# main.net
KiCad netlist of a schematic drawn in EAGLE
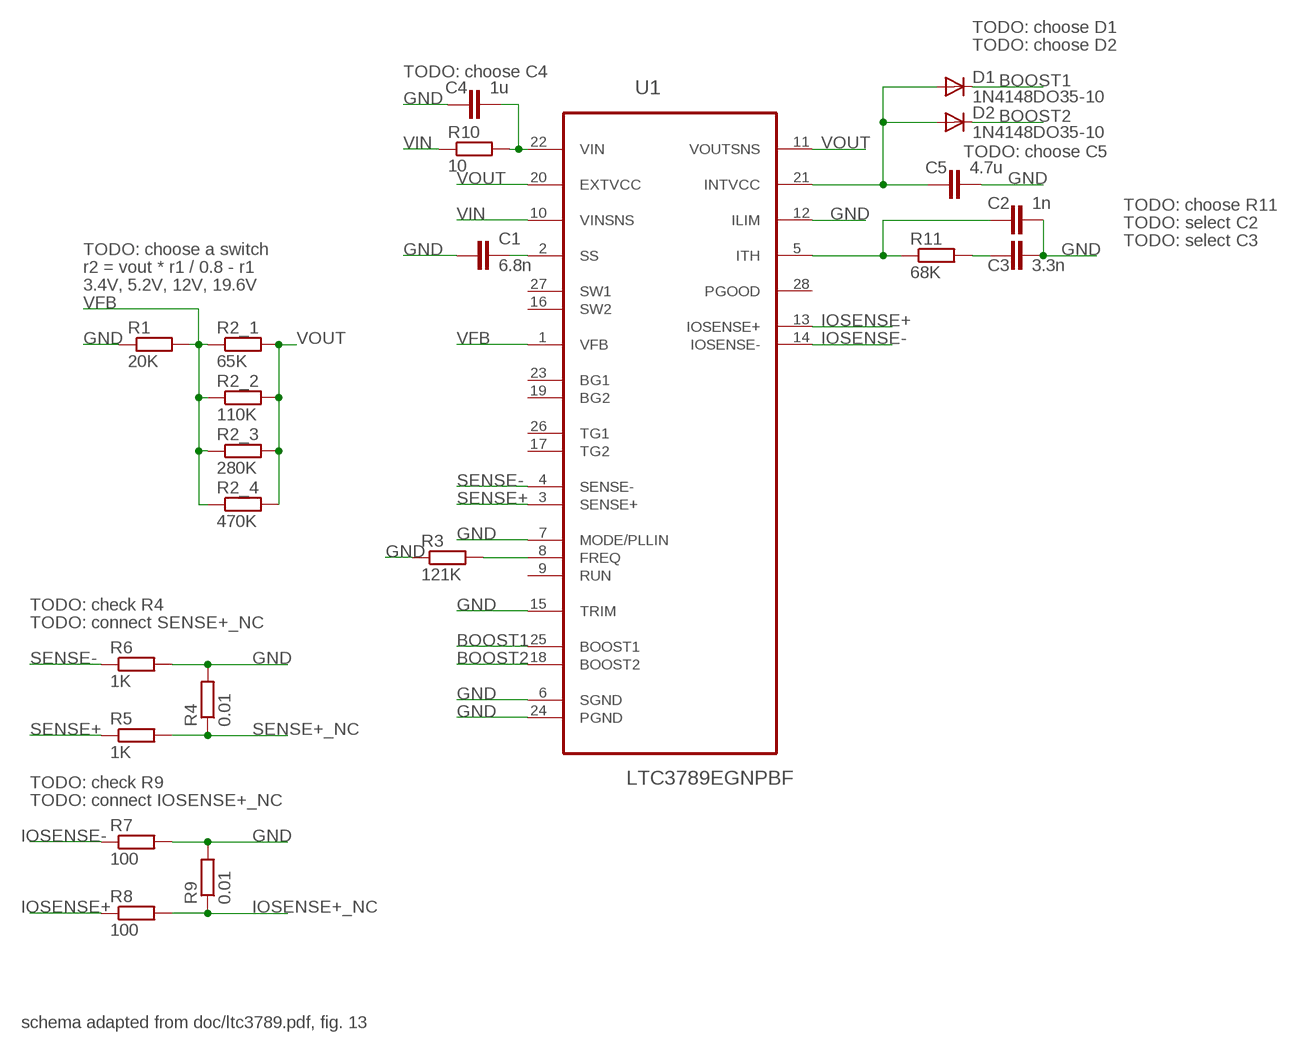
[diagram p0: schematic, sheet 1]

(export (version "E")
  (design (tool "Eeschema 10.0.6"))
  (components
    (comp (ref "C1")
      (value "6.8n")
      (footprint "eagle-import:C1206K")
      (libsource (lib "eagle-import") (part "C-EUC1206K"))
    )
    (comp (ref "C2")
      (value "1n")
      (footprint "eagle-import:C1206K")
      (libsource (lib "eagle-import") (part "C-EUC1206K"))
    )
    (comp (ref "C3")
      (value "3.3n")
      (footprint "eagle-import:C1206K")
      (libsource (lib "eagle-import") (part "C-EUC1206K"))
    )
    (comp (ref "C4")
      (value "1u")
      (footprint "eagle-import:C1206K")
      (libsource (lib "eagle-import") (part "C-EUC1206K"))
    )
    (comp (ref "C5")
      (value "4.7u")
      (footprint "eagle-import:C1206K")
      (libsource (lib "eagle-import") (part "C-EUC1206K"))
    )
    (comp (ref "D1")
      (value "1N4148DO35-10")
      (footprint "eagle-import:DO35-10")
      (libsource (lib "eagle-import") (part "1N4148DO35-10"))
    )
    (comp (ref "D2")
      (value "1N4148DO35-10")
      (footprint "eagle-import:DO35-10")
      (libsource (lib "eagle-import") (part "1N4148DO35-10"))
    )
    (comp (ref "R1")
      (value "20K")
      (footprint "eagle-import:R1206")
      (libsource (lib "eagle-import") (part "R-EU_R1206"))
    )
    (comp (ref "R2_1")
      (value "65K")
      (footprint "eagle-import:R1206")
      (libsource (lib "eagle-import") (part "R-EU_R1206"))
    )
    (comp (ref "R2_2")
      (value "110K")
      (footprint "eagle-import:R1206")
      (libsource (lib "eagle-import") (part "R-EU_R1206"))
    )
    (comp (ref "R2_3")
      (value "280K")
      (footprint "eagle-import:R1206")
      (libsource (lib "eagle-import") (part "R-EU_R1206"))
    )
    (comp (ref "R2_4")
      (value "470K")
      (footprint "eagle-import:R1206")
      (libsource (lib "eagle-import") (part "R-EU_R1206"))
    )
    (comp (ref "R3")
      (value "121K")
      (footprint "eagle-import:R1206")
      (libsource (lib "eagle-import") (part "R-EU_R1206"))
    )
    (comp (ref "R4")
      (value "0.01")
      (footprint "eagle-import:R1206")
      (libsource (lib "eagle-import") (part "R-EU_R1206"))
    )
    (comp (ref "R5")
      (value "1K")
      (footprint "eagle-import:R1206")
      (libsource (lib "eagle-import") (part "R-EU_R1206"))
    )
    (comp (ref "R6")
      (value "1K")
      (footprint "eagle-import:R1206")
      (libsource (lib "eagle-import") (part "R-EU_R1206"))
    )
    (comp (ref "R7")
      (value "100")
      (footprint "eagle-import:R1206")
      (libsource (lib "eagle-import") (part "R-EU_R1206"))
    )
    (comp (ref "R8")
      (value "100")
      (footprint "eagle-import:R1206")
      (libsource (lib "eagle-import") (part "R-EU_R1206"))
    )
    (comp (ref "R9")
      (value "0.01")
      (footprint "eagle-import:R1206")
      (libsource (lib "eagle-import") (part "R-EU_R1206"))
    )
    (comp (ref "R10")
      (value "10")
      (footprint "eagle-import:R1206")
      (libsource (lib "eagle-import") (part "R-EU_R1206"))
    )
    (comp (ref "R11")
      (value "68K")
      (footprint "eagle-import:R1206")
      (libsource (lib "eagle-import") (part "R-EU_R1206"))
    )
    (comp (ref "U1")
      (value "LTC3789EGNPBF")
      (footprint "eagle-import:SOP65P640X120-28N")
      (fields (field (name "MPN") "LTC3789EGN#PBF"))
      (libsource (lib "eagle-import") (part "LTC3789EGNPBF"))
    )
  )
  (nets
    (net (code "1") (name "/BOOST1") (class "Default")
      (node (ref "D1") (pin "C") (pinfunction "C_C") (pintype "passive"))
      (node (ref "U1") (pin "25") (pinfunction "BOOST1_25") (pintype "input"))
    )
    (net (code "2") (name "/BOOST2") (class "Default")
      (node (ref "D2") (pin "C") (pinfunction "C_C") (pintype "passive"))
      (node (ref "U1") (pin "18") (pinfunction "BOOST2_18") (pintype "input"))
    )
    (net (code "3") (name "/GND") (class "Default")
      (node (ref "C1") (pin "1") (pinfunction "1_1") (pintype "passive"))
      (node (ref "C2") (pin "2") (pinfunction "2_2") (pintype "passive"))
      (node (ref "C3") (pin "2") (pinfunction "2_2") (pintype "passive"))
      (node (ref "C4") (pin "1") (pinfunction "1_1") (pintype "passive"))
      (node (ref "C5") (pin "2") (pinfunction "2_2") (pintype "passive"))
      (node (ref "R1") (pin "1") (pinfunction "1_1") (pintype "passive"))
      (node (ref "R3") (pin "1") (pinfunction "1_1") (pintype "passive"))
      (node (ref "R4") (pin "2") (pinfunction "2_2") (pintype "passive"))
      (node (ref "R6") (pin "2") (pinfunction "2_2") (pintype "passive"))
      (node (ref "R7") (pin "2") (pinfunction "2_2") (pintype "passive"))
      (node (ref "R9") (pin "2") (pinfunction "2_2") (pintype "passive"))
      (node (ref "U1") (pin "12") (pinfunction "ILIM_12") (pintype "bidirectional"))
      (node (ref "U1") (pin "15") (pinfunction "TRIM_15") (pintype "input"))
      (node (ref "U1") (pin "24") (pinfunction "PGND_24") (pintype "passive"))
      (node (ref "U1") (pin "6") (pinfunction "SGND_6") (pintype "passive"))
      (node (ref "U1") (pin "7") (pinfunction "MODE/PLLIN_7") (pintype "input"))
    )
    (net (code "4") (name "/IOSENSE+") (class "Default")
      (node (ref "R8") (pin "1") (pinfunction "1_1") (pintype "passive"))
      (node (ref "U1") (pin "13") (pinfunction "IOSENSE+_13") (pintype "bidirectional"))
    )
    (net (code "5") (name "/IOSENSE+_NC") (class "Default")
      (node (ref "R8") (pin "2") (pinfunction "2_2") (pintype "passive"))
      (node (ref "R9") (pin "1") (pinfunction "1_1") (pintype "passive"))
    )
    (net (code "6") (name "/IOSENSE-") (class "Default")
      (node (ref "R7") (pin "1") (pinfunction "1_1") (pintype "passive"))
      (node (ref "U1") (pin "14") (pinfunction "IOSENSE-_14") (pintype "bidirectional"))
    )
    (net (code "7") (name "/SENSE+") (class "Default")
      (node (ref "R5") (pin "1") (pinfunction "1_1") (pintype "passive"))
      (node (ref "U1") (pin "3") (pinfunction "SENSE+_3") (pintype "input"))
    )
    (net (code "8") (name "/SENSE+_NC") (class "Default")
      (node (ref "R4") (pin "1") (pinfunction "1_1") (pintype "passive"))
      (node (ref "R5") (pin "2") (pinfunction "2_2") (pintype "passive"))
    )
    (net (code "9") (name "/SENSE-") (class "Default")
      (node (ref "R6") (pin "1") (pinfunction "1_1") (pintype "passive"))
      (node (ref "U1") (pin "4") (pinfunction "SENSE-_4") (pintype "input"))
    )
    (net (code "10") (name "/VFB") (class "Default")
      (node (ref "R1") (pin "2") (pinfunction "2_2") (pintype "passive"))
      (node (ref "R2_1") (pin "1") (pinfunction "1_1") (pintype "passive"))
      (node (ref "R2_2") (pin "1") (pinfunction "1_1") (pintype "passive"))
      (node (ref "R2_3") (pin "1") (pinfunction "1_1") (pintype "passive"))
      (node (ref "R2_4") (pin "1") (pinfunction "1_1") (pintype "passive"))
      (node (ref "U1") (pin "1") (pinfunction "VFB_1") (pintype "input"))
    )
    (net (code "11") (name "/VIN") (class "Default")
      (node (ref "R10") (pin "1") (pinfunction "1_1") (pintype "passive"))
      (node (ref "U1") (pin "10") (pinfunction "VINSNS_10") (pintype "input"))
    )
    (net (code "12") (name "/VOUT") (class "Default")
      (node (ref "R2_1") (pin "2") (pinfunction "2_2") (pintype "passive"))
      (node (ref "R2_2") (pin "2") (pinfunction "2_2") (pintype "passive"))
      (node (ref "R2_3") (pin "2") (pinfunction "2_2") (pintype "passive"))
      (node (ref "R2_4") (pin "2") (pinfunction "2_2") (pintype "passive"))
      (node (ref "U1") (pin "11") (pinfunction "VOUTSNS_11") (pintype "output"))
      (node (ref "U1") (pin "20") (pinfunction "EXTVCC_20") (pintype "power_in"))
    )
    (net (code "13") (name "Net-(C3-Pad1)") (class "Default")
      (node (ref "C3") (pin "1") (pinfunction "1_1") (pintype "passive"))
      (node (ref "R11") (pin "2") (pinfunction "2_2") (pintype "passive"))
    )
    (net (code "14") (name "Net-(U1-FREQ)") (class "Default")
      (node (ref "R3") (pin "2") (pinfunction "2_2") (pintype "passive"))
      (node (ref "U1") (pin "8") (pinfunction "FREQ_8") (pintype "input"))
    )
    (net (code "15") (name "Net-(U1-INTVCC)") (class "Default")
      (node (ref "C5") (pin "1") (pinfunction "1_1") (pintype "passive"))
      (node (ref "D1") (pin "A") (pinfunction "A_A") (pintype "passive"))
      (node (ref "D2") (pin "A") (pinfunction "A_A") (pintype "passive"))
      (node (ref "U1") (pin "21") (pinfunction "INTVCC_21") (pintype "output"))
    )
    (net (code "16") (name "Net-(U1-ITH)") (class "Default")
      (node (ref "C2") (pin "1") (pinfunction "1_1") (pintype "passive"))
      (node (ref "R11") (pin "1") (pinfunction "1_1") (pintype "passive"))
      (node (ref "U1") (pin "5") (pinfunction "ITH_5") (pintype "output"))
    )
    (net (code "17") (name "Net-(U1-SS)") (class "Default")
      (node (ref "C1") (pin "2") (pinfunction "2_2") (pintype "passive"))
      (node (ref "U1") (pin "2") (pinfunction "SS_2") (pintype "input"))
    )
    (net (code "18") (name "Net-(U1-VIN)") (class "Default")
      (node (ref "C4") (pin "2") (pinfunction "2_2") (pintype "passive"))
      (node (ref "R10") (pin "2") (pinfunction "2_2") (pintype "passive"))
      (node (ref "U1") (pin "22") (pinfunction "VIN_22") (pintype "power_in"))
    )
    (net (code "19") (name "unconnected-(U1-BG1-Pad23)") (class "Default")
      (node (ref "U1") (pin "23") (pinfunction "BG1_23") (pintype "input"))
    )
    (net (code "20") (name "unconnected-(U1-BG2-Pad19)") (class "Default")
      (node (ref "U1") (pin "19") (pinfunction "BG2_19") (pintype "input"))
    )
    (net (code "21") (name "unconnected-(U1-PGOOD-Pad28)") (class "Default")
      (node (ref "U1") (pin "28") (pinfunction "PGOOD_28") (pintype "output"))
    )
    (net (code "22") (name "unconnected-(U1-RUN-Pad9)") (class "Default")
      (node (ref "U1") (pin "9") (pinfunction "RUN_9") (pintype "input"))
    )
    (net (code "23") (name "unconnected-(U1-SW1-Pad27)") (class "Default")
      (node (ref "U1") (pin "27") (pinfunction "SW1_27") (pintype "input"))
    )
    (net (code "24") (name "unconnected-(U1-SW2-Pad16)") (class "Default")
      (node (ref "U1") (pin "16") (pinfunction "SW2_16") (pintype "input"))
    )
    (net (code "25") (name "unconnected-(U1-TG1-Pad26)") (class "Default")
      (node (ref "U1") (pin "26") (pinfunction "TG1_26") (pintype "input"))
    )
    (net (code "26") (name "unconnected-(U1-TG2-Pad17)") (class "Default")
      (node (ref "U1") (pin "17") (pinfunction "TG2_17") (pintype "input"))
    )
  )
)
